# Shield_x.net
KiCad netlist of a schematic drawn in EAGLE
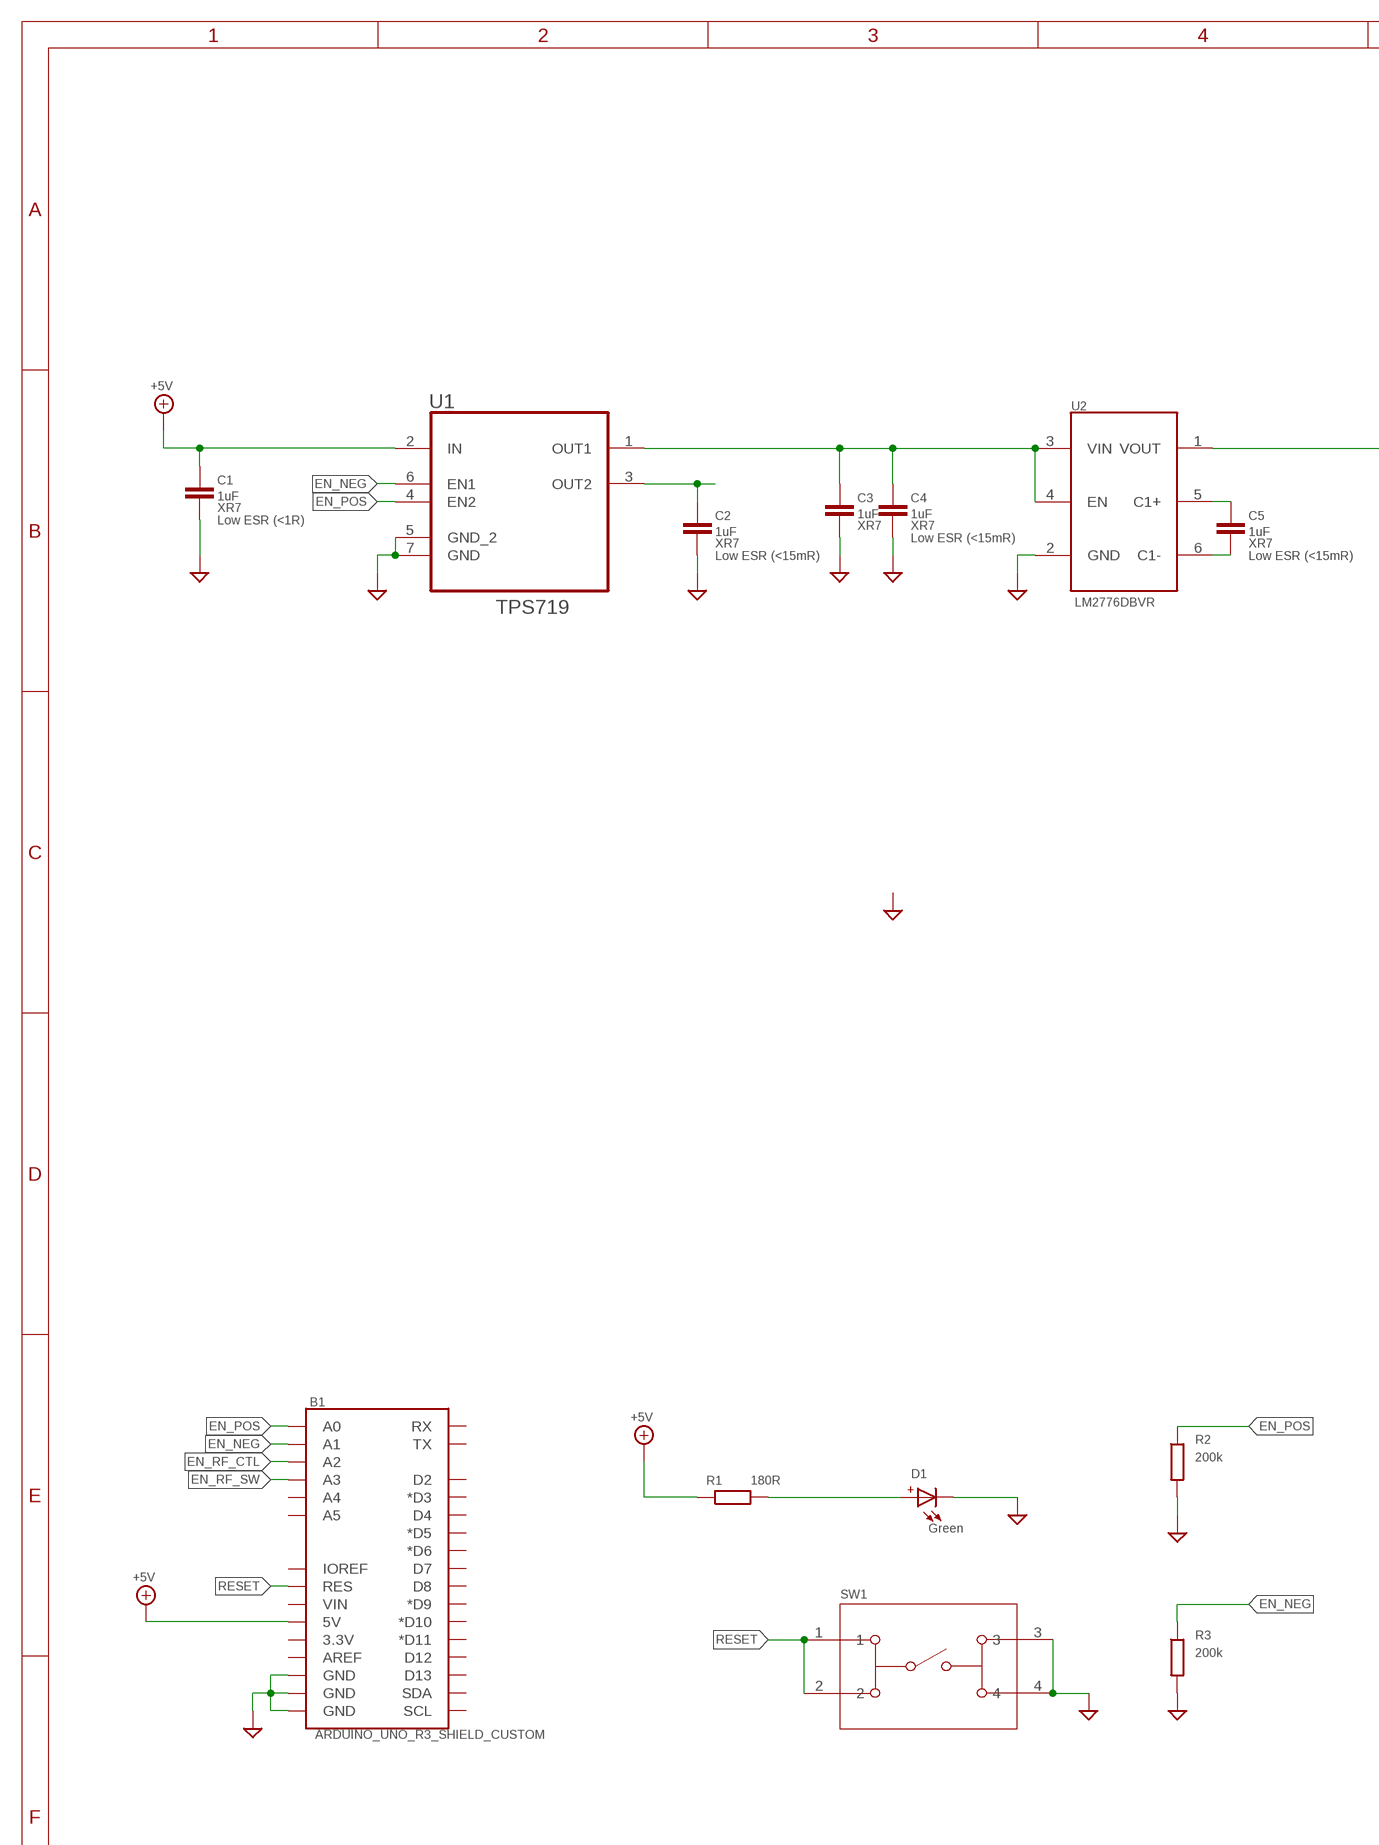
[diagram p0: schematic, sheet 1, part 1 of 2]
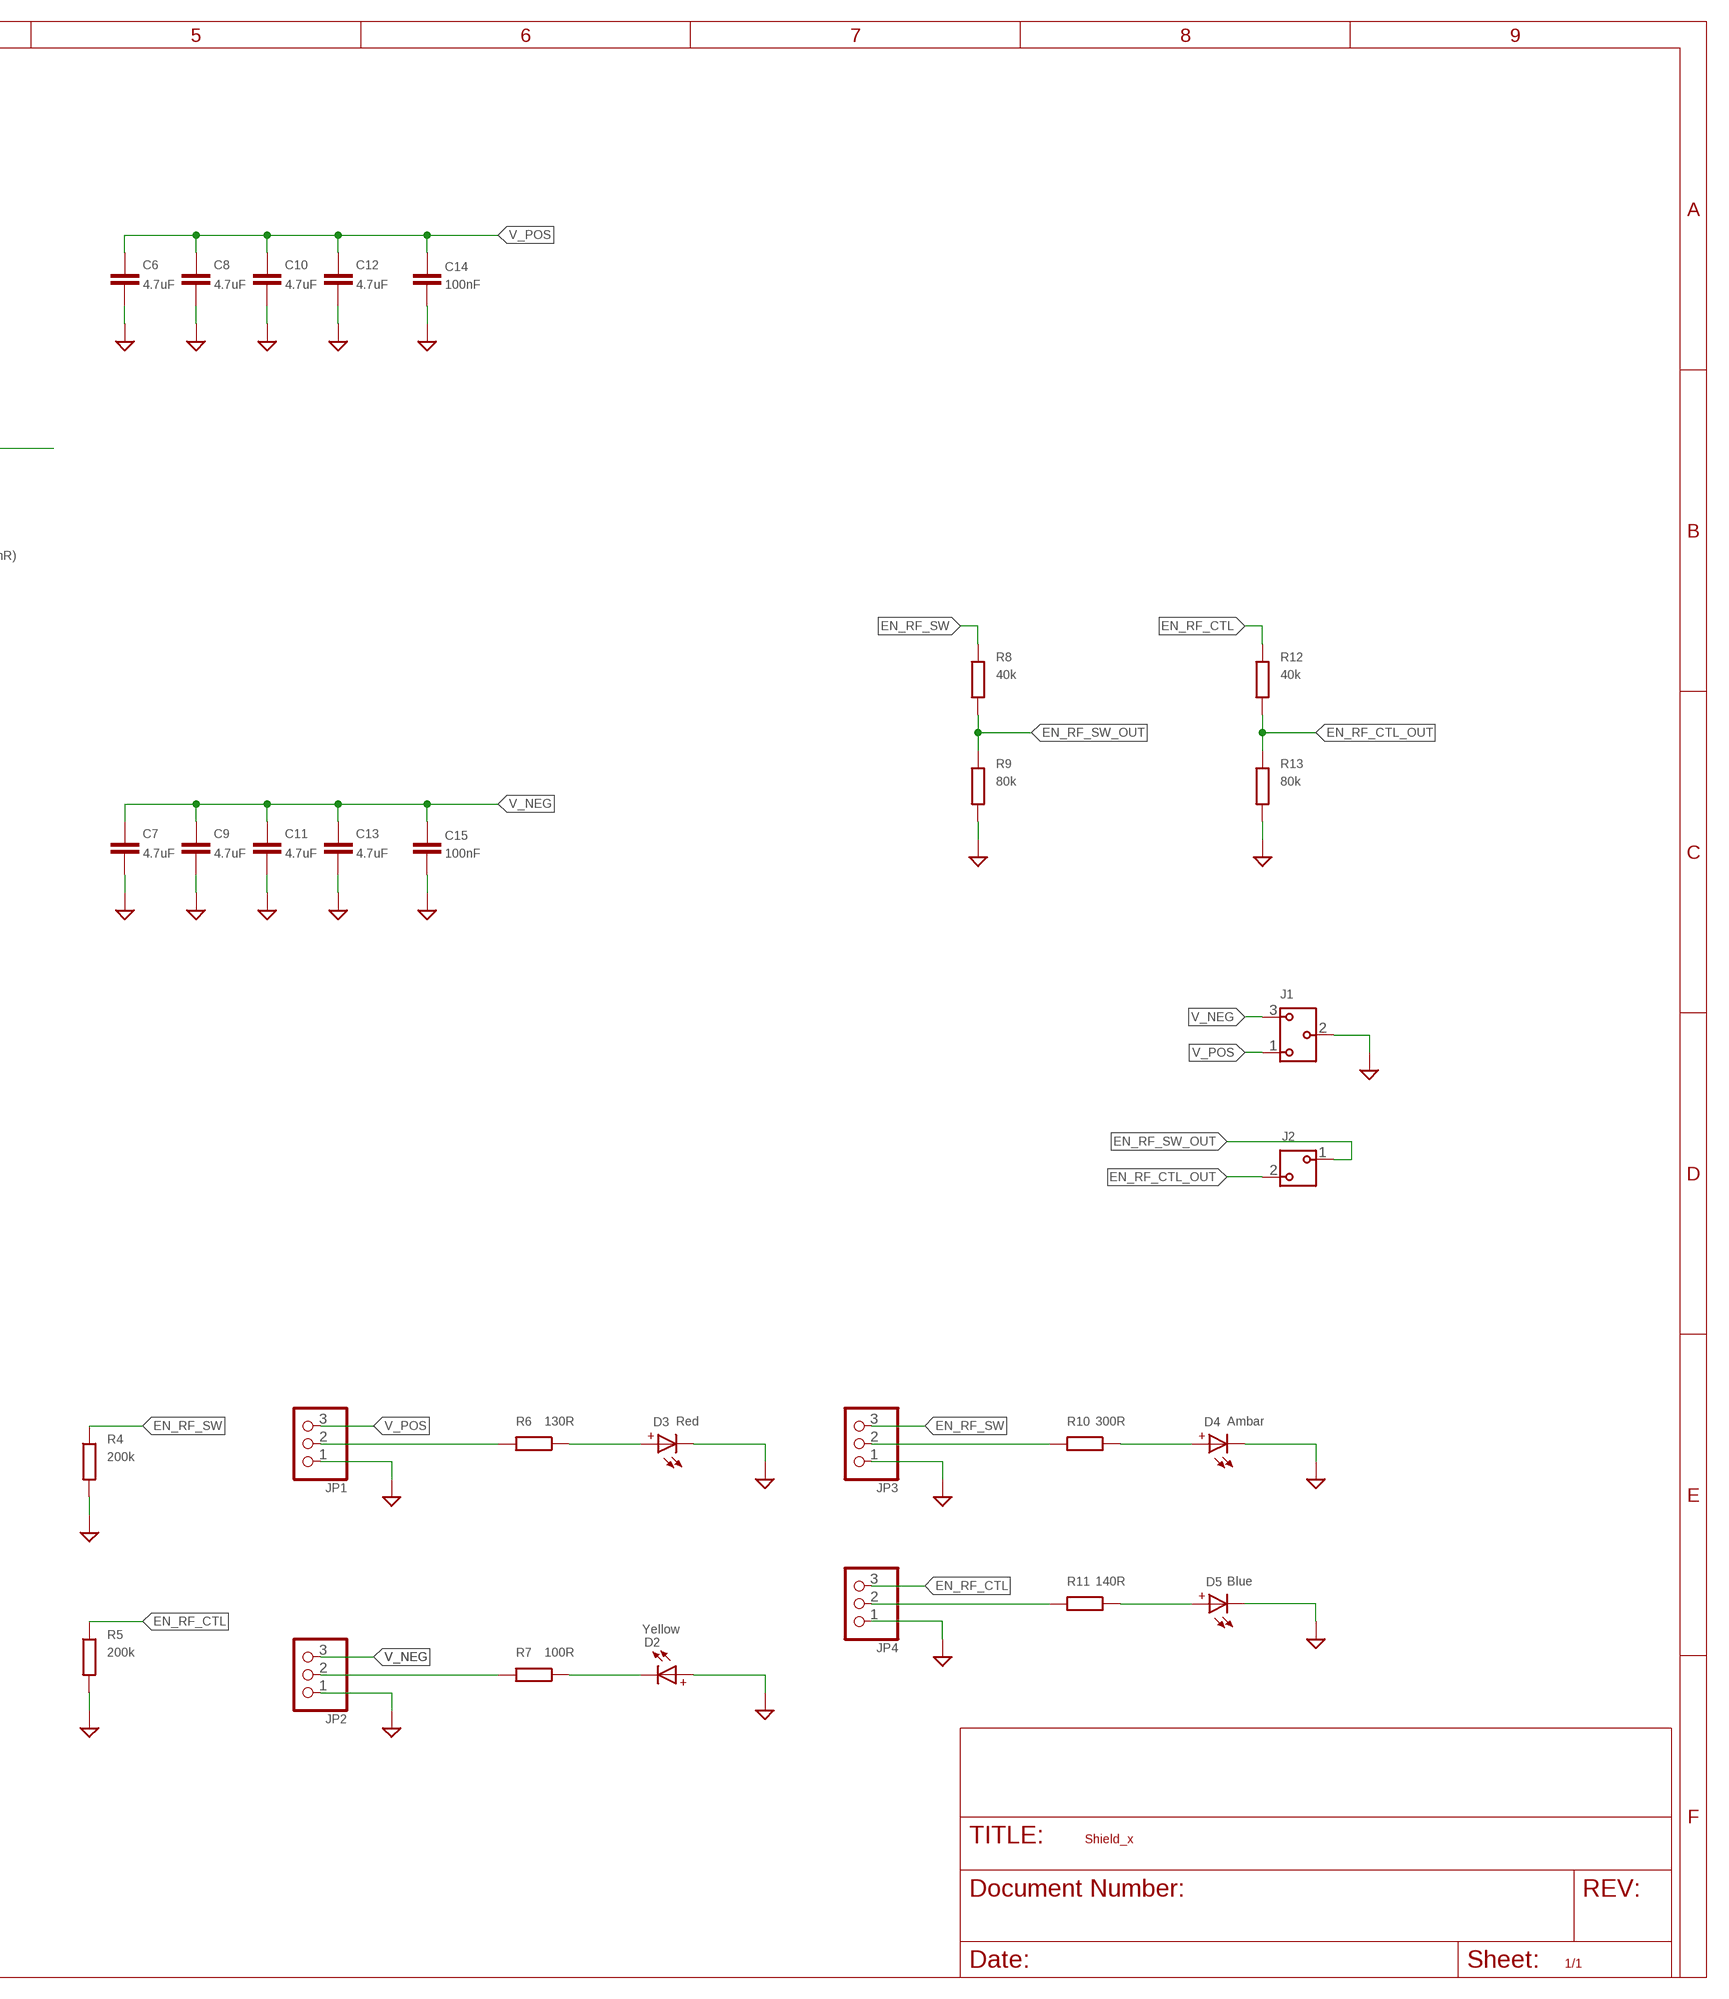
[diagram p1: schematic, sheet 1, part 2 of 2]

(export (version "E")
  (design (tool "Eeschema 10.0.6"))
  (components
    (comp (ref "B1")
      (value "ARDUINO_UNO_R3_SHIELD_CUSTOM")
      (footprint "eagle-import:UNO_R3_SHIELD_NO_PROG")
      (libsource (lib "eagle-import") (part "ARDUINO_UNO_R3_SHIELD_CUSTOM"))
    )
    (comp (ref "C1")
      (value "1uF")
      (footprint "eagle-import:C0402")
      (fields (field (name "ESR") "Low ESR (<1R)") (field (name "TYPE") "XR7"))
      (libsource (lib "eagle-import") (part "C-EUC0402"))
    )
    (comp (ref "C2")
      (value "1uF")
      (footprint "eagle-import:C0402")
      (fields (field (name "ESR") "Low ESR (<15mR)") (field (name "TYPE") "XR7"))
      (libsource (lib "eagle-import") (part "C-EUC0402"))
    )
    (comp (ref "C3")
      (value "1uF")
      (footprint "eagle-import:C0402")
      (fields (field (name "TYPE") "XR7"))
      (libsource (lib "eagle-import") (part "C-EUC0402"))
    )
    (comp (ref "C4")
      (value "1uF")
      (footprint "eagle-import:C0402")
      (fields (field (name "ESR") "Low ESR (<15mR)") (field (name "TYPE") "XR7"))
      (libsource (lib "eagle-import") (part "C-EUC0402"))
    )
    (comp (ref "C5")
      (value "1uF")
      (footprint "eagle-import:C0402")
      (fields (field (name "ESR") "Low ESR (<15mR)") (field (name "TYPE") "XR7"))
      (libsource (lib "eagle-import") (part "C-EUC0402"))
    )
    (comp (ref "C6")
      (value "4.7uF")
      (footprint "eagle-import:C1206")
      (libsource (lib "eagle-import") (part "C-EUC1206"))
    )
    (comp (ref "C7")
      (value "4.7uF")
      (footprint "eagle-import:C1206")
      (libsource (lib "eagle-import") (part "C-EUC1206"))
    )
    (comp (ref "C8")
      (value "4.7uF")
      (footprint "eagle-import:C1206")
      (libsource (lib "eagle-import") (part "C-EUC1206"))
    )
    (comp (ref "C9")
      (value "4.7uF")
      (footprint "eagle-import:C1206")
      (libsource (lib "eagle-import") (part "C-EUC1206"))
    )
    (comp (ref "C10")
      (value "4.7uF")
      (footprint "eagle-import:C1206")
      (libsource (lib "eagle-import") (part "C-EUC1206"))
    )
    (comp (ref "C11")
      (value "4.7uF")
      (footprint "eagle-import:C1206")
      (libsource (lib "eagle-import") (part "C-EUC1206"))
    )
    (comp (ref "C12")
      (value "4.7uF")
      (footprint "eagle-import:C1206")
      (libsource (lib "eagle-import") (part "C-EUC1206"))
    )
    (comp (ref "C13")
      (value "4.7uF")
      (footprint "eagle-import:C1206")
      (libsource (lib "eagle-import") (part "C-EUC1206"))
    )
    (comp (ref "C14")
      (value "100nF")
      (footprint "eagle-import:C0603")
      (libsource (lib "eagle-import") (part "C-EUC0603"))
    )
    (comp (ref "C15")
      (value "100nF")
      (footprint "eagle-import:C0603")
      (libsource (lib "eagle-import") (part "C-EUC0603"))
    )
    (comp (ref "D1")
      (value "WL-SMCW-150080GS75000")
      (footprint "eagle-import:WL-SMCW_0805")
      (fields (field (name "COLOR") "Green"))
      (libsource (lib "eagle-import") (part "WL-SMCW-150080GS75000"))
    )
    (comp (ref "D2")
      (value "WL-SMCW-150080YS75000")
      (footprint "eagle-import:WL-SMCW_0805")
      (fields (field (name "COLOR") "Yellow"))
      (libsource (lib "eagle-import") (part "WL-SMCW-150080YS75000"))
    )
    (comp (ref "D3")
      (value "WL-SMCW-150080RS75000")
      (footprint "eagle-import:WL-SMCW_0805")
      (fields (field (name "COLOR") "Red"))
      (libsource (lib "eagle-import") (part "WL-SMCW-150080RS75000"))
    )
    (comp (ref "D4")
      (value "WL-SMCW_150080AS75000")
      (footprint "eagle-import:WL-SMCW_0805")
      (fields (field (name "COLOR") "Ambar"))
      (libsource (lib "eagle-import") (part "WL-SMCW_150080AS75000"))
    )
    (comp (ref "D5")
      (value "WL-SMCW-150080BS75000")
      (footprint "eagle-import:WL-SMCW_0805")
      (fields (field (name "COLOR") "Blue"))
      (libsource (lib "eagle-import") (part "WL-SMCW-150080BS75000"))
    )
    (comp (ref "J1")
      (value "691412320003")
      (footprint "eagle-import:691412320003")
      (libsource (lib "eagle-import") (part "691412320003"))
    )
    (comp (ref "J2")
      (value "691412320002")
      (footprint "eagle-import:691412320002")
      (libsource (lib "eagle-import") (part "691412320002"))
    )
    (comp (ref "JP1")
      (value "PINHD-1X3")
      (footprint "eagle-import:1X03")
      (libsource (lib "eagle-import") (part "PINHD-1X3"))
    )
    (comp (ref "JP2")
      (value "PINHD-1X3")
      (footprint "eagle-import:1X03")
      (libsource (lib "eagle-import") (part "PINHD-1X3"))
    )
    (comp (ref "JP3")
      (value "PINHD-1X3")
      (footprint "eagle-import:1X03")
      (libsource (lib "eagle-import") (part "PINHD-1X3"))
    )
    (comp (ref "JP4")
      (value "PINHD-1X3")
      (footprint "eagle-import:1X03")
      (libsource (lib "eagle-import") (part "PINHD-1X3"))
    )
    (comp (ref "R1")
      (value "180R")
      (footprint "eagle-import:R0603")
      (libsource (lib "eagle-import") (part "R-EU_R0603"))
    )
    (comp (ref "R2")
      (value "200k")
      (footprint "eagle-import:R0603")
      (libsource (lib "eagle-import") (part "R-EU_R0603"))
    )
    (comp (ref "R3")
      (value "200k")
      (footprint "eagle-import:R0603")
      (libsource (lib "eagle-import") (part "R-EU_R0603"))
    )
    (comp (ref "R4")
      (value "200k")
      (footprint "eagle-import:R0603")
      (libsource (lib "eagle-import") (part "R-EU_R0603"))
    )
    (comp (ref "R5")
      (value "200k")
      (footprint "eagle-import:R0603")
      (libsource (lib "eagle-import") (part "R-EU_R0603"))
    )
    (comp (ref "R6")
      (value "130R")
      (footprint "eagle-import:R0603")
      (libsource (lib "eagle-import") (part "R-EU_R0603"))
    )
    (comp (ref "R7")
      (value "100R")
      (footprint "eagle-import:R0603")
      (libsource (lib "eagle-import") (part "R-EU_R0603"))
    )
    (comp (ref "R8")
      (value "40k")
      (footprint "eagle-import:R0603")
      (libsource (lib "eagle-import") (part "R-EU_R0603"))
    )
    (comp (ref "R9")
      (value "80k")
      (footprint "eagle-import:R0603")
      (libsource (lib "eagle-import") (part "R-EU_R0603"))
    )
    (comp (ref "R10")
      (value "300R")
      (footprint "eagle-import:R0603")
      (libsource (lib "eagle-import") (part "R-EU_R0603"))
    )
    (comp (ref "R11")
      (value "140R")
      (footprint "eagle-import:R0603")
      (libsource (lib "eagle-import") (part "R-EU_R0603"))
    )
    (comp (ref "R12")
      (value "40k")
      (footprint "eagle-import:R0603")
      (libsource (lib "eagle-import") (part "R-EU_R0603"))
    )
    (comp (ref "R13")
      (value "80k")
      (footprint "eagle-import:R0603")
      (libsource (lib "eagle-import") (part "R-EU_R0603"))
    )
    (comp (ref "SW1")
      (value "1825910-6")
      (footprint "eagle-import:SW4_1825910-B")
      (fields (field (name "COPYRIGHT") "Copyright (C) 2016 Accelerated Designs. All rights reserved"))
      (libsource (lib "eagle-import") (part "1825910-6"))
    )
    (comp (ref "U1")
      (value "TPS719")
      (footprint "eagle-import:SON6_5P200X200X80-7N")
      (fields (field (name "MF") "Texas Instruments"))
      (libsource (lib "eagle-import") (part "TPS719"))
    )
    (comp (ref "U2")
      (value "LM2776DBVR")
      (footprint "eagle-import:TEXAS_SOT23-6")
      (libsource (lib "eagle-import") (part "LM2776DBVR"))
    )
  )
  (nets
    (net (code "1") (name "+5V") (class "Default")
      (node (ref "B1") (pin "5V") (pinfunction "5V_5V") (pintype "bidirectional"))
      (node (ref "C1") (pin "1") (pinfunction "1_1") (pintype "passive"))
      (node (ref "R1") (pin "1") (pinfunction "1_1") (pintype "passive"))
      (node (ref "U1") (pin "2") (pinfunction "IN_2") (pintype "power_in"))
    )
    (net (code "2") (name "EN_NEG") (class "Default")
      (node (ref "B1") (pin "A1") (pinfunction "A1_A1") (pintype "bidirectional"))
      (node (ref "R3") (pin "1") (pinfunction "1_1") (pintype "passive"))
      (node (ref "U1") (pin "6") (pinfunction "EN1_6") (pintype "input"))
    )
    (net (code "3") (name "EN_POS") (class "Default")
      (node (ref "B1") (pin "A0") (pinfunction "A0_A0") (pintype "bidirectional"))
      (node (ref "R2") (pin "1") (pinfunction "1_1") (pintype "passive"))
      (node (ref "U1") (pin "4") (pinfunction "EN2_4") (pintype "input"))
    )
    (net (code "4") (name "EN_RF_CTL") (class "Default")
      (node (ref "B1") (pin "A2") (pinfunction "A2_A2") (pintype "bidirectional"))
      (node (ref "JP4") (pin "3") (pinfunction "3_3") (pintype "passive"))
      (node (ref "R12") (pin "1") (pinfunction "1_1") (pintype "passive"))
      (node (ref "R5") (pin "1") (pinfunction "1_1") (pintype "passive"))
    )
    (net (code "5") (name "EN_RF_CTL_OUT") (class "Default")
      (node (ref "J2") (pin "2") (pinfunction "2_2") (pintype "passive"))
      (node (ref "R12") (pin "2") (pinfunction "2_2") (pintype "passive"))
      (node (ref "R13") (pin "1") (pinfunction "1_1") (pintype "passive"))
    )
    (net (code "6") (name "EN_RF_SW") (class "Default")
      (node (ref "B1") (pin "A3") (pinfunction "A3_A3") (pintype "bidirectional"))
      (node (ref "JP3") (pin "3") (pinfunction "3_3") (pintype "passive"))
      (node (ref "R4") (pin "1") (pinfunction "1_1") (pintype "passive"))
      (node (ref "R8") (pin "1") (pinfunction "1_1") (pintype "passive"))
    )
    (net (code "7") (name "EN_RF_SW_OUT") (class "Default")
      (node (ref "J2") (pin "1") (pinfunction "1_1") (pintype "passive"))
      (node (ref "R8") (pin "2") (pinfunction "2_2") (pintype "passive"))
      (node (ref "R9") (pin "1") (pinfunction "1_1") (pintype "passive"))
    )
    (net (code "8") (name "GND") (class "Default")
      (node (ref "B1") (pin "GND@0") (pinfunction "GND_GND@0") (pintype "bidirectional"))
      (node (ref "B1") (pin "GND@1") (pinfunction "GND_GND@1") (pintype "bidirectional"))
      (node (ref "B1") (pin "GND@2") (pinfunction "GND_GND@2") (pintype "bidirectional"))
      (node (ref "C1") (pin "2") (pinfunction "2_2") (pintype "passive"))
      (node (ref "C10") (pin "2") (pinfunction "2_2") (pintype "passive"))
      (node (ref "C11") (pin "2") (pinfunction "2_2") (pintype "passive"))
      (node (ref "C12") (pin "2") (pinfunction "2_2") (pintype "passive"))
      (node (ref "C13") (pin "2") (pinfunction "2_2") (pintype "passive"))
      (node (ref "C14") (pin "2") (pinfunction "2_2") (pintype "passive"))
      (node (ref "C15") (pin "2") (pinfunction "2_2") (pintype "passive"))
      (node (ref "C2") (pin "2") (pinfunction "2_2") (pintype "passive"))
      (node (ref "C3") (pin "2") (pinfunction "2_2") (pintype "passive"))
      (node (ref "C4") (pin "2") (pinfunction "2_2") (pintype "passive"))
      (node (ref "C6") (pin "2") (pinfunction "2_2") (pintype "passive"))
      (node (ref "C7") (pin "2") (pinfunction "2_2") (pintype "passive"))
      (node (ref "C8") (pin "2") (pinfunction "2_2") (pintype "passive"))
      (node (ref "C9") (pin "2") (pinfunction "2_2") (pintype "passive"))
      (node (ref "D1") (pin "1") (pinfunction "-_1") (pintype "passive"))
      (node (ref "D2") (pin "2") (pinfunction "+_2") (pintype "passive"))
      (node (ref "D3") (pin "1") (pinfunction "-_1") (pintype "passive"))
      (node (ref "D4") (pin "1") (pinfunction "-_1") (pintype "passive"))
      (node (ref "D5") (pin "1") (pinfunction "-_1") (pintype "passive"))
      (node (ref "J1") (pin "2") (pinfunction "2_2") (pintype "passive"))
      (node (ref "JP1") (pin "1") (pinfunction "1_1") (pintype "passive"))
      (node (ref "JP2") (pin "1") (pinfunction "1_1") (pintype "passive"))
      (node (ref "JP3") (pin "1") (pinfunction "1_1") (pintype "passive"))
      (node (ref "JP4") (pin "1") (pinfunction "1_1") (pintype "passive"))
      (node (ref "R13") (pin "2") (pinfunction "2_2") (pintype "passive"))
      (node (ref "R2") (pin "2") (pinfunction "2_2") (pintype "passive"))
      (node (ref "R3") (pin "2") (pinfunction "2_2") (pintype "passive"))
      (node (ref "R4") (pin "2") (pinfunction "2_2") (pintype "passive"))
      (node (ref "R5") (pin "2") (pinfunction "2_2") (pintype "passive"))
      (node (ref "R9") (pin "2") (pinfunction "2_2") (pintype "passive"))
      (node (ref "SW1") (pin "3") (pinfunction "3_3") (pintype "passive"))
      (node (ref "SW1") (pin "4") (pinfunction "4_4") (pintype "passive"))
      (node (ref "U1") (pin "5") (pinfunction "GND_2_5") (pintype "passive"))
      (node (ref "U1") (pin "7") (pinfunction "GND_7") (pintype "passive"))
      (node (ref "U2") (pin "2") (pinfunction "GND_2") (pintype "bidirectional"))
    )
    (net (code "9") (name "Net-(D1-+)") (class "Default")
      (node (ref "D1") (pin "2") (pinfunction "+_2") (pintype "passive"))
      (node (ref "R1") (pin "2") (pinfunction "2_2") (pintype "passive"))
    )
    (net (code "10") (name "Net-(D2--)") (class "Default")
      (node (ref "D2") (pin "1") (pinfunction "-_1") (pintype "passive"))
      (node (ref "R7") (pin "1") (pinfunction "1_1") (pintype "passive"))
    )
    (net (code "11") (name "Net-(D3-+)") (class "Default")
      (node (ref "D3") (pin "2") (pinfunction "+_2") (pintype "passive"))
      (node (ref "R6") (pin "1") (pinfunction "1_1") (pintype "passive"))
    )
    (net (code "12") (name "Net-(D4-+)") (class "Default")
      (node (ref "D4") (pin "2") (pinfunction "+_2") (pintype "passive"))
      (node (ref "R10") (pin "1") (pinfunction "1_1") (pintype "passive"))
    )
    (net (code "13") (name "Net-(D5-+)") (class "Default")
      (node (ref "D5") (pin "2") (pinfunction "+_2") (pintype "passive"))
      (node (ref "R11") (pin "1") (pinfunction "1_1") (pintype "passive"))
    )
    (net (code "14") (name "Net-(JP1-Pad2)") (class "Default")
      (node (ref "JP1") (pin "2") (pinfunction "2_2") (pintype "passive"))
      (node (ref "R6") (pin "2") (pinfunction "2_2") (pintype "passive"))
    )
    (net (code "15") (name "Net-(JP2-Pad2)") (class "Default")
      (node (ref "JP2") (pin "2") (pinfunction "2_2") (pintype "passive"))
      (node (ref "R7") (pin "2") (pinfunction "2_2") (pintype "passive"))
    )
    (net (code "16") (name "Net-(JP3-Pad2)") (class "Default")
      (node (ref "JP3") (pin "2") (pinfunction "2_2") (pintype "passive"))
      (node (ref "R10") (pin "2") (pinfunction "2_2") (pintype "passive"))
    )
    (net (code "17") (name "Net-(JP4-Pad2)") (class "Default")
      (node (ref "JP4") (pin "2") (pinfunction "2_2") (pintype "passive"))
      (node (ref "R11") (pin "2") (pinfunction "2_2") (pintype "passive"))
    )
    (net (code "18") (name "Net-(U1-OUT1)") (class "Default")
      (node (ref "C3") (pin "1") (pinfunction "1_1") (pintype "passive"))
      (node (ref "C4") (pin "1") (pinfunction "1_1") (pintype "passive"))
      (node (ref "U1") (pin "1") (pinfunction "OUT1_1") (pintype "output"))
      (node (ref "U2") (pin "3") (pinfunction "VIN_3") (pintype "bidirectional"))
      (node (ref "U2") (pin "4") (pinfunction "EN_4") (pintype "bidirectional"))
    )
    (net (code "19") (name "Net-(U1-OUT2)") (class "Default")
      (node (ref "C2") (pin "1") (pinfunction "1_1") (pintype "passive"))
      (node (ref "U1") (pin "3") (pinfunction "OUT2_3") (pintype "output"))
    )
    (net (code "20") (name "Net-(U2-C1+)") (class "Default")
      (node (ref "C5") (pin "1") (pinfunction "1_1") (pintype "passive"))
      (node (ref "U2") (pin "5") (pinfunction "C1+_5") (pintype "bidirectional"))
    )
    (net (code "21") (name "Net-(U2-C1-)") (class "Default")
      (node (ref "C5") (pin "2") (pinfunction "2_2") (pintype "passive"))
      (node (ref "U2") (pin "6") (pinfunction "C1-_6") (pintype "bidirectional"))
    )
    (net (code "22") (name "RESET") (class "Default")
      (node (ref "B1") (pin "RES") (pinfunction "RES_RES") (pintype "bidirectional"))
      (node (ref "SW1") (pin "1") (pinfunction "1_1") (pintype "passive"))
      (node (ref "SW1") (pin "2") (pinfunction "2_2") (pintype "passive"))
    )
    (net (code "23") (name "V_NEG") (class "Default")
      (node (ref "C11") (pin "1") (pinfunction "1_1") (pintype "passive"))
      (node (ref "C13") (pin "1") (pinfunction "1_1") (pintype "passive"))
      (node (ref "C15") (pin "1") (pinfunction "1_1") (pintype "passive"))
      (node (ref "C7") (pin "1") (pinfunction "1_1") (pintype "passive"))
      (node (ref "C9") (pin "1") (pinfunction "1_1") (pintype "passive"))
      (node (ref "J1") (pin "3") (pinfunction "3_3") (pintype "passive"))
      (node (ref "JP2") (pin "3") (pinfunction "3_3") (pintype "passive"))
    )
    (net (code "24") (name "V_POS") (class "Default")
      (node (ref "C10") (pin "1") (pinfunction "1_1") (pintype "passive"))
      (node (ref "C12") (pin "1") (pinfunction "1_1") (pintype "passive"))
      (node (ref "C14") (pin "1") (pinfunction "1_1") (pintype "passive"))
      (node (ref "C6") (pin "1") (pinfunction "1_1") (pintype "passive"))
      (node (ref "C8") (pin "1") (pinfunction "1_1") (pintype "passive"))
      (node (ref "J1") (pin "1") (pinfunction "1_1") (pintype "passive"))
      (node (ref "JP1") (pin "3") (pinfunction "3_3") (pintype "passive"))
    )
    (net (code "25") (name "unconnected-(B1-*D3-PadD3)") (class "Default")
      (node (ref "B1") (pin "D3") (pinfunction "*D3_D3") (pintype "bidirectional"))
    )
    (net (code "26") (name "unconnected-(B1-*D5-PadD5)") (class "Default")
      (node (ref "B1") (pin "D5") (pinfunction "*D5_D5") (pintype "bidirectional"))
    )
    (net (code "27") (name "unconnected-(B1-*D6-PadD6)") (class "Default")
      (node (ref "B1") (pin "D6") (pinfunction "*D6_D6") (pintype "bidirectional"))
    )
    (net (code "28") (name "unconnected-(B1-*D9-PadD9)") (class "Default")
      (node (ref "B1") (pin "D9") (pinfunction "*D9_D9") (pintype "bidirectional"))
    )
    (net (code "29") (name "unconnected-(B1-*D10-PadD10)") (class "Default")
      (node (ref "B1") (pin "D10") (pinfunction "*D10_D10") (pintype "bidirectional"))
    )
    (net (code "30") (name "unconnected-(B1-*D11-PadD11)") (class "Default")
      (node (ref "B1") (pin "D11") (pinfunction "*D11_D11") (pintype "bidirectional"))
    )
    (net (code "31") (name "unconnected-(B1-Pad3.3V)") (class "Default")
      (node (ref "B1") (pin "3.3V") (pinfunction "3.3V_3.3V") (pintype "bidirectional"))
    )
    (net (code "32") (name "unconnected-(B1-PadA4)") (class "Default")
      (node (ref "B1") (pin "A4") (pinfunction "A4_A4") (pintype "bidirectional"))
    )
    (net (code "33") (name "unconnected-(B1-PadA5)") (class "Default")
      (node (ref "B1") (pin "A5") (pinfunction "A5_A5") (pintype "bidirectional"))
    )
    (net (code "34") (name "unconnected-(B1-PadAREF)") (class "Default")
      (node (ref "B1") (pin "AREF") (pinfunction "AREF_AREF") (pintype "bidirectional"))
    )
    (net (code "35") (name "unconnected-(B1-PadD2)") (class "Default")
      (node (ref "B1") (pin "D2") (pinfunction "D2_D2") (pintype "bidirectional"))
    )
    (net (code "36") (name "unconnected-(B1-PadD4)") (class "Default")
      (node (ref "B1") (pin "D4") (pinfunction "D4_D4") (pintype "bidirectional"))
    )
    (net (code "37") (name "unconnected-(B1-PadD7)") (class "Default")
      (node (ref "B1") (pin "D7") (pinfunction "D7_D7") (pintype "bidirectional"))
    )
    (net (code "38") (name "unconnected-(B1-PadD8)") (class "Default")
      (node (ref "B1") (pin "D8") (pinfunction "D8_D8") (pintype "bidirectional"))
    )
    (net (code "39") (name "unconnected-(B1-PadD12)") (class "Default")
      (node (ref "B1") (pin "D12") (pinfunction "D12_D12") (pintype "bidirectional"))
    )
    (net (code "40") (name "unconnected-(B1-PadD13)") (class "Default")
      (node (ref "B1") (pin "D13") (pinfunction "D13_D13") (pintype "bidirectional"))
    )
    (net (code "41") (name "unconnected-(B1-PadIOREF)") (class "Default")
      (node (ref "B1") (pin "IOREF") (pinfunction "IOREF_IOREF") (pintype "bidirectional"))
    )
    (net (code "42") (name "unconnected-(B1-PadRX)") (class "Default")
      (node (ref "B1") (pin "RX") (pinfunction "RX_RX") (pintype "bidirectional"))
    )
    (net (code "43") (name "unconnected-(B1-PadSCL)") (class "Default")
      (node (ref "B1") (pin "SCL") (pinfunction "SCL_SCL") (pintype "bidirectional"))
    )
    (net (code "44") (name "unconnected-(B1-PadSDA)") (class "Default")
      (node (ref "B1") (pin "SDA") (pinfunction "SDA_SDA") (pintype "bidirectional"))
    )
    (net (code "45") (name "unconnected-(B1-PadTX)") (class "Default")
      (node (ref "B1") (pin "TX") (pinfunction "TX_TX") (pintype "bidirectional"))
    )
    (net (code "46") (name "unconnected-(B1-PadVIN)") (class "Default")
      (node (ref "B1") (pin "VIN") (pinfunction "VIN_VIN") (pintype "bidirectional"))
    )
    (net (code "47") (name "unconnected-(U2-VOUT-Pad1)") (class "Default")
      (node (ref "U2") (pin "1") (pinfunction "VOUT_1") (pintype "bidirectional"))
    )
  )
)
